# ESP32.net
KiCad netlist of a schematic drawn in Altium Designer
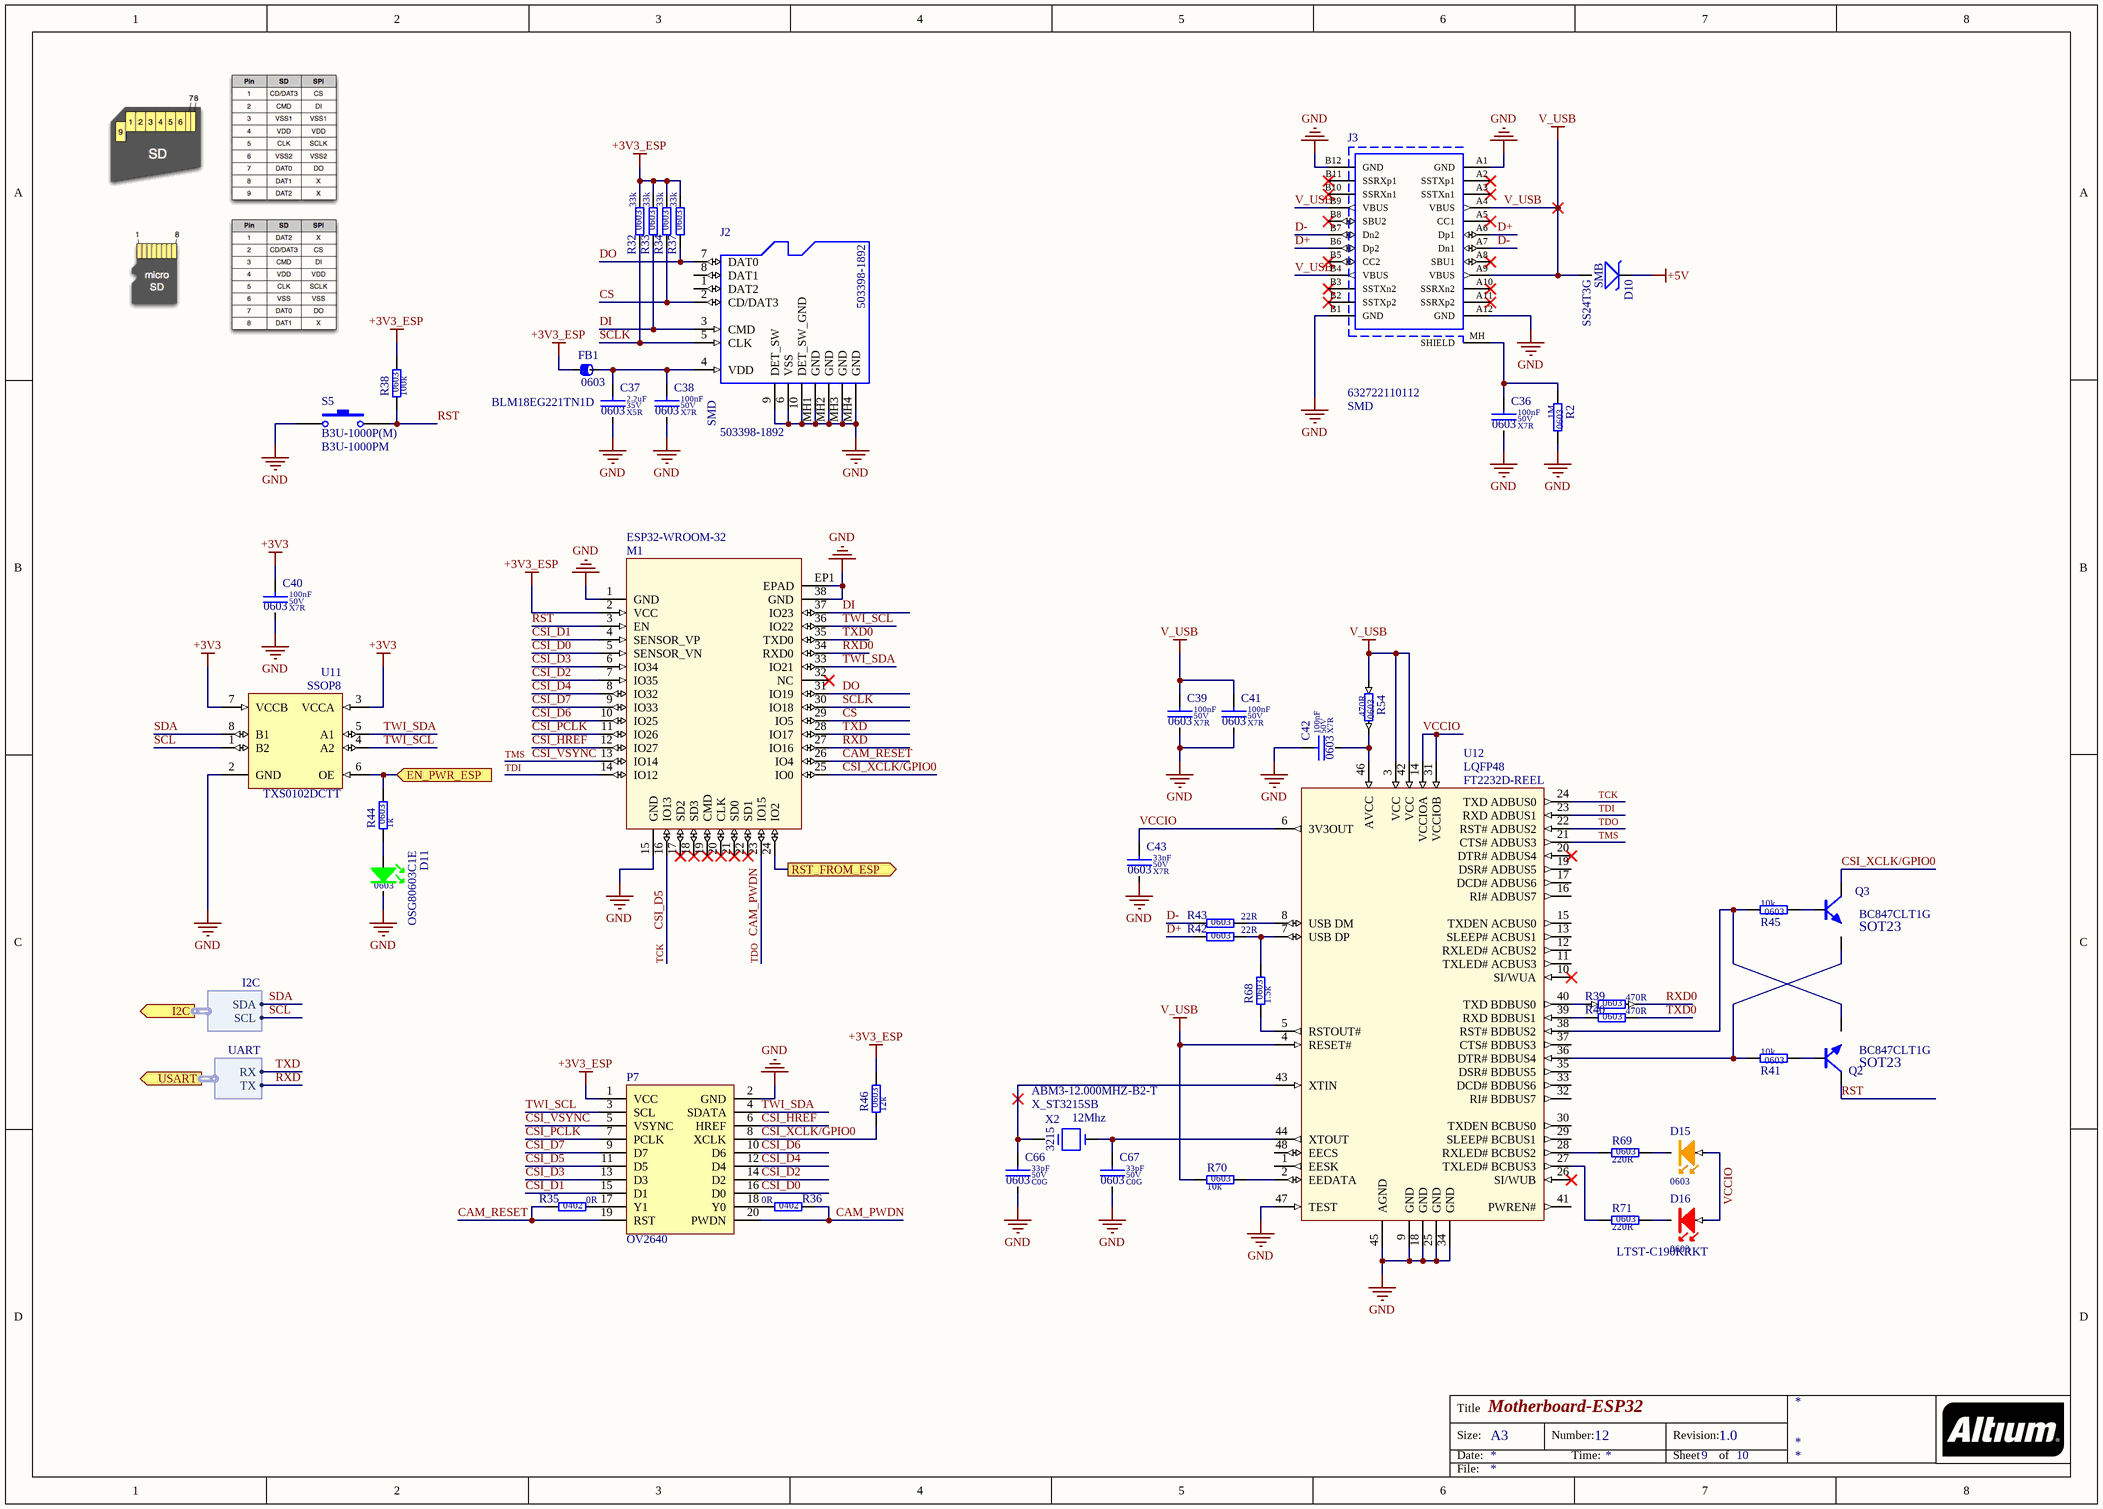
[diagram p0: ESP32.SchDoc]

(export (version "E")
  (design (tool "Eeschema 10.0.6"))
  (components
    (comp (ref "C36")
      (value "100nF")
      (footprint "C_0603_1608")
      (description "Capacitor")
      (fields
        (field (name "DIELECTRIC") "X7R")
        (field (name "VOLTAGE") "50V")
        (field (name "SCH_FOOTPRINT") "0603")
        (field (name "PART NUMBER") "C_100nF_50V_X7R_0603_5")
        (field (name "MANUFACTURER") "Samsung")
      )
      (libsource (lib "Library") (part "C"))
    )
    (comp (ref "C37")
      (value "2.2uF")
      (footprint "C_0603_1608")
      (description "Capacitor")
      (fields
        (field (name "DIELECTRIC") "X5R")
        (field (name "VOLTAGE") "35V")
        (field (name "SCH_FOOTPRINT") "0603")
        (field (name "PART NUMBER") "C_2.2uF_35V_X5R_0603_10")
        (field (name "MANUFACTURER") "Murata")
      )
      (libsource (lib "Library") (part "C"))
    )
    (comp (ref "C38")
      (value "100nF")
      (footprint "C_0603_1608")
      (description "Capacitor")
      (fields
        (field (name "DIELECTRIC") "X7R")
        (field (name "VOLTAGE") "50V")
        (field (name "SCH_FOOTPRINT") "0603")
        (field (name "PART NUMBER") "C_100nF_50V_X7R_0603_5")
        (field (name "MANUFACTURER") "Samsung")
      )
      (libsource (lib "Library") (part "C"))
    )
    (comp (ref "C39")
      (value "100nF")
      (footprint "C_0603_1608")
      (description "Capacitor")
      (fields
        (field (name "DIELECTRIC") "X7R")
        (field (name "VOLTAGE") "50V")
        (field (name "SCH_FOOTPRINT") "0603")
        (field (name "PART NUMBER") "C_100nF_50V_X7R_0603_5")
        (field (name "MANUFACTURER") "Samsung")
      )
      (libsource (lib "Library") (part "C"))
    )
    (comp (ref "C40")
      (value "100nF")
      (footprint "C_0603_1608")
      (description "Capacitor")
      (fields
        (field (name "DIELECTRIC") "X7R")
        (field (name "VOLTAGE") "50V")
        (field (name "SCH_FOOTPRINT") "0603")
        (field (name "PART NUMBER") "C_100nF_50V_X7R_0603_5")
        (field (name "MANUFACTURER") "Samsung")
      )
      (libsource (lib "Library") (part "C"))
    )
    (comp (ref "C41")
      (value "100nF")
      (footprint "C_0603_1608")
      (description "Capacitor")
      (fields
        (field (name "DIELECTRIC") "X7R")
        (field (name "VOLTAGE") "50V")
        (field (name "SCH_FOOTPRINT") "0603")
        (field (name "PART NUMBER") "C_100nF_50V_X7R_0603_5")
        (field (name "MANUFACTURER") "Samsung")
      )
      (libsource (lib "Library") (part "C"))
    )
    (comp (ref "C42")
      (value "100nF")
      (footprint "C_0603_1608")
      (description "Capacitor")
      (fields
        (field (name "DIELECTRIC") "X7R")
        (field (name "VOLTAGE") "50V")
        (field (name "SCH_FOOTPRINT") "0603")
        (field (name "PART NUMBER") "C_100nF_50V_X7R_0603_5")
        (field (name "MANUFACTURER") "Samsung")
      )
      (libsource (lib "Library") (part "C"))
    )
    (comp (ref "C43")
      (value "33nF")
      (footprint "C_0603_1608")
      (description "Capacitor")
      (fields
        (field (name "DIELECTRIC") "X7R")
        (field (name "VOLTAGE") "50V")
        (field (name "SCH_FOOTPRINT") "0603")
        (field (name "PART NUMBER") "C_33nF_50V_X7R_0603_10")
        (field (name "MANUFACTURER") "Yageo")
      )
      (libsource (lib "Library") (part "C"))
    )
    (comp (ref "C66")
      (value "33pF")
      (footprint "C_0603_1608")
      (description "Capacitor")
      (fields
        (field (name "DIELECTRIC") "C0G")
        (field (name "VOLTAGE") "50V")
        (field (name "SCH_FOOTPRINT") "0603")
        (field (name "PART NUMBER") "C_33pF_50V_C0G_0603_5")
        (field (name "MANUFACTURER") "AVX")
      )
      (libsource (lib "Library") (part "C"))
    )
    (comp (ref "C67")
      (value "33pF")
      (footprint "C_0603_1608")
      (description "Capacitor")
      (fields
        (field (name "DIELECTRIC") "C0G")
        (field (name "VOLTAGE") "50V")
        (field (name "SCH_FOOTPRINT") "0603")
        (field (name "PART NUMBER") "C_33pF_50V_C0G_0603_5")
        (field (name "MANUFACTURER") "AVX")
      )
      (libsource (lib "Library") (part "C"))
    )
    (comp (ref "D10")
      (value "SS24T3G")
      (footprint "SMB_DO-214AA")
      (fields
        (field (name "SCH_FOOTPRINT") "SMB")
        (field (name "PART NUMBER") "DS_SS24_2A_40V_SMB")
        (field (name "VOLTAGE") "40V")
        (field (name "MANUFACTURER") "ON Semiconductor")
      )
      (libsource (lib "Library") (part "DS"))
    )
    (comp (ref "D11")
      (value "OSG80603C1E")
      (footprint "OL_0603_1608")
      (description "LED GREEN")
      (fields
        (field (name "SCH_FOOTPRINT") "0603")
        (field (name "PART NUMBER") "OL_G_0603_OSG80603C1E")
        (field (name "MANUFACTURER") "Optosupply")
      )
      (libsource (lib "Library") (part "OL_G"))
    )
    (comp (ref "D15")
      (value "OL_O")
      (footprint "OL_0603_1608")
      (description "LED_RED")
      (fields (field (name "PART NUMBER") "OL_O_0603") (field (name "SCH_FOOTPRINT") "0603"))
      (libsource (lib "Library") (part "OL_O"))
    )
    (comp (ref "D16")
      (value "LTST-C190KRKT")
      (footprint "OL_0603_1608")
      (description "LED_RED")
      (fields
        (field (name "PART NUMBER") "OL_R_0603")
        (field (name "SCH_FOOTPRINT") "0603")
        (field (name "MANUFACTURER") "Lite-On")
      )
      (libsource (lib "Library") (part "OL_R"))
    )
    (comp (ref "FB1")
      (value "BLM18EG221TN1D")
      (footprint "FB_0603_1608")
      (description "Ferrite Bead")
      (fields
        (field (name "PART NUMBER") "FB_BLM18EG221TN1D")
        (field (name "SCH_FOOTPRINT") "0603")
        (field (name "MANUFACTURER") "Murata")
      )
      (libsource (lib "Library") (part "FB"))
    )
    (comp (ref "J2")
      (value "503398-1892")
      (footprint "503398-1892")
      (description "J_MICRO_SD")
      (fields
        (field (name "SCH_FOOTPRINT") "SMD")
        (field (name "MANUFACTURER PART NUMBER") "503398-1892")
        (field (name "PART NUMBER") "J_MICRO_SD_503398-1892")
        (field (name "MANUFACTURER") "Molex")
      )
      (libsource (lib "Library") (part "J_MICRO_SD_503398-1892"))
    )
    (comp (ref "J3")
      (value "632722110112")
      (footprint "J_USB_C_3.1_Vertical")
      (fields
        (field (name "PART NUMBER") "J_USB_C_3.1_Vertical")
        (field (name "SCH_FOOTPRINT") "SMD")
        (field (name "MANUFACTURER") "Wurth")
        (field (name "Comment") "USB C Connector")
      )
      (libsource (lib "Library") (part "J_USB_3.1_C"))
    )
    (comp (ref "M1")
      (value "ESP32-WROOM-32")
      (footprint "MOD_ESP_WROOM_32")
      (fields
        (field (name "PART NUMBER") "MOD_ESP32-WROOM-32")
        (field (name "MANUFACTURER") "ESPRESSIF")
        (field (name "Comment") "2.4 GHz Wi-Fi-and-Bluetooth combo chip")
      )
      (libsource (lib "Library") (part "MOD_ESP_WROOM_32"))
    )
    (comp (ref "P7")
      (value "OV2640")
      (footprint "H2X10_OV2640")
      (description "Header, 11-Pin, Dual row, Right Angle")
      (fields (field (name "PUBLISHER") "Altium Limited"))
      (libsource (lib "Patryk_ROZNE") (part "OV2640"))
    )
    (comp (ref "Q2")
      (value "BC847CLT1G")
      (footprint "SOT23_TO236_SC59")
      (fields
        (field (name "PART NUMBER") "QNP_BC847C_45V_0A1")
        (field (name "SCH_FOOTPRINT") "SOT23")
        (field (name "VOLTAGE") "45V")
        (field (name "MANUFACTURER") "ON Semiconductor")
      )
      (libsource (lib "Library") (part "QNP_BEC"))
    )
    (comp (ref "Q3")
      (value "BC847CLT1G")
      (footprint "SOT23_TO236_SC59")
      (fields
        (field (name "PART NUMBER") "QNP_BC847C_45V_0A1")
        (field (name "SCH_FOOTPRINT") "SOT23")
        (field (name "VOLTAGE") "45V")
        (field (name "MANUFACTURER") "ON Semiconductor")
      )
      (libsource (lib "Library") (part "QNP_BEC"))
    )
    (comp (ref "R2")
      (value "1M")
      (footprint "R_0603_1608")
      (fields
        (field (name "SCH_FOOTPRINT") "0603")
        (field (name "PART NUMBER") "R_1M_0603_1")
        (field (name "VOLTAGE") "50V")
        (field (name "POWER") "100mW")
      )
      (libsource (lib "Library") (part "R"))
    )
    (comp (ref "R32")
      (value "33k")
      (footprint "R_0603_1608")
      (fields
        (field (name "SCH_FOOTPRINT") "0603")
        (field (name "PART NUMBER") "R_33k_0603_1")
        (field (name "VOLTAGE") "75V")
        (field (name "POWER") "100mW")
      )
      (libsource (lib "Library") (part "R"))
    )
    (comp (ref "R33")
      (value "33k")
      (footprint "R_0603_1608")
      (fields
        (field (name "SCH_FOOTPRINT") "0603")
        (field (name "PART NUMBER") "R_33k_0603_1")
        (field (name "VOLTAGE") "75V")
        (field (name "POWER") "100mW")
      )
      (libsource (lib "Library") (part "R"))
    )
    (comp (ref "R34")
      (value "33k")
      (footprint "R_0603_1608")
      (fields
        (field (name "SCH_FOOTPRINT") "0603")
        (field (name "PART NUMBER") "R_33k_0603_1")
        (field (name "VOLTAGE") "75V")
        (field (name "POWER") "100mW")
      )
      (libsource (lib "Library") (part "R"))
    )
    (comp (ref "R35")
      (value "0R")
      (footprint "R_0402_1005")
      (fields
        (field (name "SCH_FOOTPRINT") "0402")
        (field (name "PART NUMBER") "R_0R_0402_5")
        (field (name "VOLTAGE") "50V")
        (field (name "POWER") "63mW")
      )
      (libsource (lib "Library") (part "R"))
    )
    (comp (ref "R36")
      (value "0R")
      (footprint "R_0402_1005")
      (fields
        (field (name "SCH_FOOTPRINT") "0402")
        (field (name "PART NUMBER") "R_0R_0402_5")
        (field (name "VOLTAGE") "50V")
        (field (name "POWER") "63mW")
      )
      (libsource (lib "Library") (part "R"))
    )
    (comp (ref "R37")
      (value "33k")
      (footprint "R_0603_1608")
      (fields
        (field (name "SCH_FOOTPRINT") "0603")
        (field (name "PART NUMBER") "R_33k_0603_1")
        (field (name "VOLTAGE") "75V")
        (field (name "POWER") "100mW")
      )
      (libsource (lib "Library") (part "R"))
    )
    (comp (ref "R38")
      (value "100k")
      (footprint "R_0603_1608")
      (fields
        (field (name "SCH_FOOTPRINT") "0603")
        (field (name "PART NUMBER") "R_100k_0603_1")
        (field (name "VOLTAGE") "50V")
        (field (name "POWER") "100mW")
      )
      (libsource (lib "Library") (part "R"))
    )
    (comp (ref "R39")
      (value "470R")
      (footprint "R_0603_1608")
      (fields
        (field (name "SCH_FOOTPRINT") "0603")
        (field (name "PART NUMBER") "R_470R_0603_1")
        (field (name "VOLTAGE") "50V")
        (field (name "POWER") "100mW")
      )
      (libsource (lib "") (part "R_2"))
    )
    (comp (ref "R40")
      (value "470R")
      (footprint "R_0603_1608")
      (fields
        (field (name "SCH_FOOTPRINT") "0603")
        (field (name "PART NUMBER") "R_470R_0603_1")
        (field (name "VOLTAGE") "50V")
        (field (name "POWER") "100mW")
      )
      (libsource (lib "") (part "R_1"))
    )
    (comp (ref "R41")
      (value "10k")
      (footprint "R_0603_1608")
      (fields
        (field (name "SCH_FOOTPRINT") "0603")
        (field (name "PART NUMBER") "R_10k_0603_1")
        (field (name "VOLTAGE") "75V")
        (field (name "POWER") "100mW")
      )
      (libsource (lib "Library") (part "R"))
    )
    (comp (ref "R42")
      (value "22R")
      (footprint "R_0603_1608")
      (fields
        (field (name "SCH_FOOTPRINT") "0603")
        (field (name "PART NUMBER") "R_22R_0603_5")
        (field (name "VOLTAGE") "50V")
        (field (name "POWER") "125mW")
      )
      (libsource (lib "Library") (part "R"))
    )
    (comp (ref "R43")
      (value "22R")
      (footprint "R_0603_1608")
      (fields
        (field (name "SCH_FOOTPRINT") "0603")
        (field (name "PART NUMBER") "R_22R_0603_5")
        (field (name "VOLTAGE") "50V")
        (field (name "POWER") "125mW")
      )
      (libsource (lib "Library") (part "R"))
    )
    (comp (ref "R44")
      (value "1k")
      (footprint "R_0603_1608")
      (fields
        (field (name "SCH_FOOTPRINT") "0603")
        (field (name "PART NUMBER") "R_1k_0603_1")
        (field (name "VOLTAGE") "75V")
        (field (name "POWER") "100mW")
      )
      (libsource (lib "Library") (part "R"))
    )
    (comp (ref "R45")
      (value "10k")
      (footprint "R_0603_1608")
      (fields
        (field (name "SCH_FOOTPRINT") "0603")
        (field (name "PART NUMBER") "R_10k_0603_1")
        (field (name "VOLTAGE") "75V")
        (field (name "POWER") "100mW")
      )
      (libsource (lib "Library") (part "R"))
    )
    (comp (ref "R46")
      (value "12k")
      (footprint "R_0603_1608")
      (fields
        (field (name "SCH_FOOTPRINT") "0603")
        (field (name "PART NUMBER") "R_12k_0603_1")
        (field (name "VOLTAGE") "50V")
        (field (name "POWER") "100mW")
      )
      (libsource (lib "Library") (part "R"))
    )
    (comp (ref "R54")
      (value "470R")
      (footprint "R_0603_1608")
      (fields
        (field (name "SCH_FOOTPRINT") "0603")
        (field (name "PART NUMBER") "R_470R_0603_1")
        (field (name "VOLTAGE") "50V")
        (field (name "POWER") "100mW")
      )
      (libsource (lib "") (part "R_2"))
    )
    (comp (ref "R68")
      (value "1.5k")
      (footprint "R_0603_1608")
      (fields
        (field (name "SCH_FOOTPRINT") "0603")
        (field (name "PART NUMBER") "R_1.5k_0603_1")
        (field (name "VOLTAGE") "50V")
        (field (name "POWER") "100mW")
      )
      (libsource (lib "Library") (part "R"))
    )
    (comp (ref "R69")
      (value "220R")
      (footprint "R_0603_1608")
      (fields
        (field (name "SCH_FOOTPRINT") "0603")
        (field (name "PART NUMBER") "R_220R_0603_1")
        (field (name "VOLTAGE") "50V")
        (field (name "POWER") "100mW")
      )
      (libsource (lib "Library") (part "R"))
    )
    (comp (ref "R70")
      (value "10k")
      (footprint "R_0603_1608")
      (fields
        (field (name "SCH_FOOTPRINT") "0603")
        (field (name "PART NUMBER") "R_10k_0603_1")
        (field (name "VOLTAGE") "75V")
        (field (name "POWER") "100mW")
      )
      (libsource (lib "Library") (part "R"))
    )
    (comp (ref "R71")
      (value "220R")
      (footprint "R_0603_1608")
      (fields
        (field (name "SCH_FOOTPRINT") "0603")
        (field (name "PART NUMBER") "R_220R_0603_1")
        (field (name "VOLTAGE") "50V")
        (field (name "POWER") "100mW")
      )
      (libsource (lib "Library") (part "R"))
    )
    (comp (ref "S5")
      (value "B3U-1000PM")
      (footprint "B3U-1000P")
      (description "Tact Switch")
      (fields
        (field (name "PART NUMBER") "S_B3U-1000PM")
        (field (name "SCH_FOOTPRINT") "B3U-1000P(M)")
        (field (name "MANUFACTURER") "OMRON")
      )
      (libsource (lib "Library") (part "S_TACTSWITCH"))
    )
    (comp (ref "U11")
      (value "TXS0102DCTT")
      (footprint "SSOP8_3x3")
      (fields
        (field (name "SCH_FOOTPRINT") "SSOP8")
        (field (name "PART NUMBER") "U_TXS0102DCTT")
        (field (name "MANUFACTURER") "Texas Instruments")
      )
      (libsource (lib "Library") (part "U_TXS0102_DCT_DCU"))
    )
    (comp (ref "U12")
      (value "FT2232D-REEL")
      (footprint "LQFP48_7x7")
      (description "FTDI")
      (fields
        (field (name "SCH_FOOTPRINT") "LQFP48")
        (field (name "PART NUMBER") "U_FT2232D")
        (field (name "Comment") "FT2232D")
      )
      (libsource (lib "Library") (part "U_FT2232D"))
    )
    (comp (ref "X2")
      (value "12Mhz")
      (footprint "X_ABM3-12.000MHZ-B2-T")
      (fields
        (field (name "PART NUMBER") "X_ABM3-12.000MHZ-B2-T")
        (field (name "MANUFACTURER PART NUMBER") "ABM3-12.000MHZ-B2-T")
        (field (name "SCH_FOOTPRINT") "X_ST3215SB")
        (field (name "MANUFACTURER") "ABM3")
        (field (name "Comment") "X_ST3215SB")
      )
      (libsource (lib "Library") (part "X_ST3215SB"))
    )
  )
  (nets
    (net (code "3") (name "+3V3") (class "Default")
      (node (ref "C40") (pin "1") (pinfunction "1_1") (pintype "passive"))
      (node (ref "U11") (pin "3") (pinfunction "VCCA_3") (pintype "input"))
      (node (ref "U11") (pin "7") (pinfunction "VCCB_7") (pintype "input"))
    )
    (net (code "4") (name "+3V3_ESP") (class "Default")
      (node (ref "FB1") (pin "1") (pintype "passive"))
      (node (ref "M1") (pin "2") (pinfunction "VCC_2") (pintype "input"))
      (node (ref "P7") (pin "1") (pinfunction "VCC_1") (pintype "passive"))
      (node (ref "R32") (pin "2") (pinfunction "2_2") (pintype "passive"))
      (node (ref "R33") (pin "2") (pinfunction "2_2") (pintype "passive"))
      (node (ref "R34") (pin "2") (pinfunction "2_2") (pintype "passive"))
      (node (ref "R37") (pin "2") (pinfunction "2_2") (pintype "passive"))
      (node (ref "R38") (pin "2") (pinfunction "2_2") (pintype "passive"))
      (node (ref "R46") (pin "2") (pinfunction "2_2") (pintype "passive"))
    )
    (net (code "5") (name "+5V") (class "Default") (node (ref "D10") (pin "1") (pintype "passive")))
    (net (code "6") (name "/CAM_PWDN") (class "Default")
      (node (ref "M1") (pin "23") (pinfunction "IO15_23") (pintype "bidirectional"))
      (node (ref "P7") (pin "20") (pinfunction "PWDN_20") (pintype "passive"))
      (node (ref "R36") (pin "2") (pinfunction "2_2") (pintype "passive"))
      (node (ref "U12") (pin "22") (pinfunction "RST#_ADBUS2_22") (pintype "input"))
    )
    (net (code "7") (name "/CAM_RESET") (class "Default")
      (node (ref "M1") (pin "26") (pinfunction "IO4_26") (pintype "bidirectional"))
      (node (ref "P7") (pin "19") (pinfunction "RST_19") (pintype "passive"))
      (node (ref "R35") (pin "1") (pinfunction "1_1") (pintype "passive"))
    )
    (net (code "8") (name "/CS") (class "Default")
      (node (ref "J2") (pin "2") (pinfunction "CD/DAT3_2") (pintype "bidirectional"))
      (node (ref "M1") (pin "29") (pinfunction "IO5_29") (pintype "bidirectional"))
      (node (ref "R34") (pin "1") (pinfunction "1_1") (pintype "passive"))
    )
    (net (code "9") (name "/CSI_D0") (class "Default")
      (node (ref "M1") (pin "5") (pinfunction "SENSOR_VN_5") (pintype "input"))
      (node (ref "P7") (pin "16") (pinfunction "D0_16") (pintype "passive"))
    )
    (net (code "10") (name "/CSI_D1") (class "Default")
      (node (ref "M1") (pin "4") (pinfunction "SENSOR_VP_4") (pintype "input"))
      (node (ref "P7") (pin "15") (pinfunction "D1_15") (pintype "passive"))
    )
    (net (code "11") (name "/CSI_D2") (class "Default")
      (node (ref "M1") (pin "7") (pinfunction "IO35_7") (pintype "input"))
      (node (ref "P7") (pin "14") (pinfunction "D2_14") (pintype "passive"))
    )
    (net (code "12") (name "/CSI_D3") (class "Default")
      (node (ref "M1") (pin "6") (pinfunction "IO34_6") (pintype "input"))
      (node (ref "P7") (pin "13") (pinfunction "D3_13") (pintype "passive"))
    )
    (net (code "13") (name "/CSI_D4") (class "Default")
      (node (ref "M1") (pin "8") (pinfunction "IO32_8") (pintype "bidirectional"))
      (node (ref "P7") (pin "12") (pinfunction "D4_12") (pintype "passive"))
    )
    (net (code "14") (name "/CSI_D5") (class "Default")
      (node (ref "M1") (pin "16") (pinfunction "IO13_16") (pintype "bidirectional"))
      (node (ref "P7") (pin "11") (pinfunction "D5_11") (pintype "passive"))
      (node (ref "U12") (pin "24") (pinfunction "TXD_ADBUS0_24") (pintype "output"))
    )
    (net (code "15") (name "/CSI_D6") (class "Default")
      (node (ref "M1") (pin "10") (pinfunction "IO25_10") (pintype "bidirectional"))
      (node (ref "P7") (pin "10") (pinfunction "D6_10") (pintype "passive"))
    )
    (net (code "16") (name "/CSI_D7") (class "Default")
      (node (ref "M1") (pin "9") (pinfunction "IO33_9") (pintype "bidirectional"))
      (node (ref "P7") (pin "9") (pinfunction "D7_9") (pintype "passive"))
    )
    (net (code "17") (name "/CSI_HREF") (class "Default")
      (node (ref "M1") (pin "12") (pinfunction "IO27_12") (pintype "bidirectional"))
      (node (ref "P7") (pin "6") (pinfunction "HREF_6") (pintype "passive"))
    )
    (net (code "18") (name "/CSI_PCLK") (class "Default")
      (node (ref "M1") (pin "11") (pinfunction "IO26_11") (pintype "bidirectional"))
      (node (ref "P7") (pin "7") (pinfunction "PCLK_7") (pintype "passive"))
    )
    (net (code "19") (name "/CSI_VSYNC") (class "Default")
      (node (ref "M1") (pin "13") (pinfunction "IO14_13") (pintype "bidirectional"))
      (node (ref "P7") (pin "5") (pinfunction "VSYNC_5") (pintype "passive"))
      (node (ref "U12") (pin "21") (pinfunction "CTS#_ADBUS3_21") (pintype "output"))
    )
    (net (code "20") (name "/CSI_XCLK{slash}GPIO0") (class "Default")
      (node (ref "M1") (pin "25") (pinfunction "IO0_25") (pintype "bidirectional"))
      (node (ref "P7") (pin "8") (pinfunction "XCLK_8") (pintype "passive"))
      (node (ref "Q3") (pin "3") (pinfunction "C_3") (pintype "passive"))
      (node (ref "R46") (pin "1") (pinfunction "1_1") (pintype "passive"))
    )
    (net (code "21") (name "/D+") (class "Default")
      (node (ref "J3") (pin "A6") (pinfunction "Dp1_A6") (pintype "bidirectional"))
      (node (ref "J3") (pin "B6") (pinfunction "Dp2_B6") (pintype "bidirectional"))
      (node (ref "R42") (pin "1") (pinfunction "1_1") (pintype "passive"))
    )
    (net (code "22") (name "/D-") (class "Default")
      (node (ref "J3") (pin "A7") (pinfunction "Dn1_A7") (pintype "bidirectional"))
      (node (ref "J3") (pin "B7") (pinfunction "Dn2_B7") (pintype "bidirectional"))
      (node (ref "R43") (pin "1") (pinfunction "1_1") (pintype "passive"))
    )
    (net (code "23") (name "/DI") (class "Default")
      (node (ref "J2") (pin "3") (pinfunction "CMD_3") (pintype "input"))
      (node (ref "M1") (pin "37") (pinfunction "IO23_37") (pintype "bidirectional"))
      (node (ref "R33") (pin "1") (pinfunction "1_1") (pintype "passive"))
    )
    (net (code "24") (name "/DO") (class "Default")
      (node (ref "J2") (pin "7") (pinfunction "DAT0_7") (pintype "bidirectional"))
      (node (ref "M1") (pin "31") (pinfunction "IO19_31") (pintype "bidirectional"))
      (node (ref "R37") (pin "1") (pinfunction "1_1") (pintype "passive"))
    )
    (net (code "25") (name "/EN_PWR_ESP") (class "Default")
      (node (ref "R44") (pin "2") (pinfunction "2_2") (pintype "passive"))
      (node (ref "U11") (pin "6") (pinfunction "OE_6") (pintype "input"))
    )
    (net (code "26") (name "/RST") (class "Default")
      (node (ref "M1") (pin "3") (pinfunction "EN_3") (pintype "input"))
      (node (ref "Q2") (pin "3") (pinfunction "C_3") (pintype "passive"))
      (node (ref "R38") (pin "1") (pinfunction "1_1") (pintype "passive"))
      (node (ref "S5") (pin "2") (pinfunction "2_2") (pintype "passive"))
    )
    (net (code "27") (name "/RST_FROM_ESP") (class "Default")
      (node (ref "M1") (pin "24") (pinfunction "IO2_24") (pintype "bidirectional"))
    )
    (net (code "28") (name "/RXD") (class "Default")
      (node (ref "M1") (pin "27") (pinfunction "IO16_27") (pintype "bidirectional"))
    )
    (net (code "29") (name "/RXD0") (class "Default")
      (node (ref "M1") (pin "34") (pinfunction "RXD0_34") (pintype "bidirectional"))
      (node (ref "R39") (pin "2") (pinfunction "2_2") (pintype "output"))
    )
    (net (code "30") (name "/SCL") (class "Default")
      (node (ref "U11") (pin "1") (pinfunction "B2_1") (pintype "bidirectional"))
    )
    (net (code "31") (name "/SCLK") (class "Default")
      (node (ref "J2") (pin "5") (pinfunction "CLK_5") (pintype "input"))
      (node (ref "M1") (pin "30") (pinfunction "IO18_30") (pintype "bidirectional"))
      (node (ref "R32") (pin "1") (pinfunction "1_1") (pintype "passive"))
    )
    (net (code "32") (name "/SDA") (class "Default")
      (node (ref "U11") (pin "8") (pinfunction "B1_8") (pintype "bidirectional"))
    )
    (net (code "33") (name "/TDI") (class "Default")
      (node (ref "M1") (pin "14") (pinfunction "IO12_14") (pintype "bidirectional"))
      (node (ref "U12") (pin "23") (pinfunction "RXD_ADBUS1_23") (pintype "input"))
    )
    (net (code "34") (name "/TWI_SCL") (class "Default")
      (node (ref "M1") (pin "36") (pinfunction "IO22_36") (pintype "bidirectional"))
      (node (ref "P7") (pin "3") (pinfunction "SCL_3") (pintype "passive"))
      (node (ref "U11") (pin "4") (pinfunction "A2_4") (pintype "bidirectional"))
    )
    (net (code "35") (name "/TWI_SDA") (class "Default")
      (node (ref "M1") (pin "33") (pinfunction "IO21_33") (pintype "bidirectional"))
      (node (ref "P7") (pin "4") (pinfunction "SDATA_4") (pintype "passive"))
      (node (ref "U11") (pin "5") (pinfunction "A1_5") (pintype "bidirectional"))
    )
    (net (code "36") (name "/TXD") (class "Default")
      (node (ref "M1") (pin "28") (pinfunction "IO17_28") (pintype "bidirectional"))
    )
    (net (code "37") (name "/TXD0") (class "Default")
      (node (ref "M1") (pin "35") (pinfunction "TXD0_35") (pintype "bidirectional"))
      (node (ref "R40") (pin "2") (pinfunction "2_2") (pintype "bidirectional"))
    )
    (net (code "38") (name "/VCCIO") (class "Default")
      (node (ref "C43") (pin "1") (pinfunction "1_1") (pintype "passive"))
      (node (ref "D15") (pin "2") (pinfunction "A_2") (pintype "input"))
      (node (ref "D16") (pin "2") (pinfunction "A_2") (pintype "input"))
      (node (ref "U12") (pin "14") (pinfunction "VCCIOA_14") (pintype "input"))
      (node (ref "U12") (pin "31") (pinfunction "VCCIOB_31") (pintype "input"))
      (node (ref "U12") (pin "6") (pinfunction "3V3OUT_6") (pintype "output"))
    )
    (net (code "41") (name "GND") (class "Default")
      (node (ref "C36") (pin "2") (pinfunction "2_2") (pintype "passive"))
      (node (ref "C37") (pin "2") (pinfunction "2_2") (pintype "passive"))
      (node (ref "C38") (pin "2") (pinfunction "2_2") (pintype "passive"))
      (node (ref "C39") (pin "2") (pinfunction "2_2") (pintype "passive"))
      (node (ref "C40") (pin "2") (pinfunction "2_2") (pintype "passive"))
      (node (ref "C41") (pin "2") (pinfunction "2_2") (pintype "passive"))
      (node (ref "C42") (pin "1") (pinfunction "1_1") (pintype "passive"))
      (node (ref "C43") (pin "2") (pinfunction "2_2") (pintype "passive"))
      (node (ref "C66") (pin "2") (pinfunction "2_2") (pintype "passive"))
      (node (ref "C67") (pin "2") (pinfunction "2_2") (pintype "passive"))
      (node (ref "D11") (pin "1") (pinfunction "K_1") (pintype "passive"))
      (node (ref "J2") (pin "10") (pinfunction "DET_SW_GND_10") (pintype "power_in"))
      (node (ref "J2") (pin "6") (pinfunction "VSS_6") (pintype "power_in"))
      (node (ref "J2") (pin "9") (pinfunction "DET_SW_9") (pintype "passive"))
      (node (ref "J2") (pin "MH1") (pinfunction "GND_MH1") (pintype "power_in"))
      (node (ref "J2") (pin "MH2") (pinfunction "GND_MH2") (pintype "power_in"))
      (node (ref "J2") (pin "MH3") (pinfunction "GND_MH3") (pintype "power_in"))
      (node (ref "J2") (pin "MH4") (pinfunction "GND_MH4") (pintype "power_in"))
      (node (ref "J3") (pin "A1") (pinfunction "GND_A1") (pintype "power_in"))
      (node (ref "J3") (pin "A12") (pinfunction "GND_A12") (pintype "power_in"))
      (node (ref "J3") (pin "B1") (pinfunction "GND_B1") (pintype "power_in"))
      (node (ref "J3") (pin "B12") (pinfunction "GND_B12") (pintype "power_in"))
      (node (ref "M1") (pin "1") (pinfunction "GND_1") (pintype "power_in"))
      (node (ref "M1") (pin "15") (pinfunction "GND_15") (pintype "power_in"))
      (node (ref "M1") (pin "38") (pinfunction "GND_38") (pintype "power_in"))
      (node (ref "M1") (pin "EP1") (pinfunction "EPAD_EP1") (pintype "power_in"))
      (node (ref "P7") (pin "2") (pinfunction "GND_2") (pintype "passive"))
      (node (ref "R2") (pin "2") (pinfunction "2_2") (pintype "passive"))
      (node (ref "S5") (pin "1") (pinfunction "1_1") (pintype "passive"))
      (node (ref "U11") (pin "2") (pinfunction "GND_2") (pintype "power_in"))
      (node (ref "U12") (pin "18") (pinfunction "GND_18") (pintype "power_in"))
      (node (ref "U12") (pin "25") (pinfunction "GND_25") (pintype "power_in"))
      (node (ref "U12") (pin "34") (pinfunction "GND_34") (pintype "power_in"))
      (node (ref "U12") (pin "45") (pinfunction "AGND_45") (pintype "power_in"))
      (node (ref "U12") (pin "47") (pinfunction "TEST_47") (pintype "input"))
      (node (ref "U12") (pin "9") (pinfunction "GND_9") (pintype "power_in"))
    )
    (net (code "42") (name "Net-(D11-A)") (class "Default")
      (node (ref "D11") (pin "2") (pinfunction "A_2") (pintype "passive"))
      (node (ref "R44") (pin "1") (pinfunction "1_1") (pintype "passive"))
    )
    (net (code "43") (name "Net-(D15-K)") (class "Default")
      (node (ref "D15") (pin "1") (pinfunction "K_1") (pintype "output"))
      (node (ref "R69") (pin "2") (pinfunction "2_2") (pintype "passive"))
    )
    (net (code "44") (name "Net-(D16-K)") (class "Default")
      (node (ref "D16") (pin "1") (pinfunction "K_1") (pintype "output"))
      (node (ref "R71") (pin "2") (pinfunction "2_2") (pintype "passive"))
    )
    (net (code "45") (name "Net-(J2-VDD)") (class "Default")
      (node (ref "C37") (pin "1") (pinfunction "1_1") (pintype "passive"))
      (node (ref "C38") (pin "1") (pinfunction "1_1") (pintype "passive"))
      (node (ref "FB1") (pin "2") (pintype "passive"))
      (node (ref "J2") (pin "4") (pinfunction "VDD_4") (pintype "input"))
    )
    (net (code "46") (name "Net-(J3-SHIELD)") (class "Default")
      (node (ref "C36") (pin "1") (pinfunction "1_1") (pintype "passive"))
      (node (ref "J3") (pin "MH") (pinfunction "SHIELD_MH") (pintype "passive"))
      (node (ref "R2") (pin "1") (pinfunction "1_1") (pintype "passive"))
    )
    (net (code "47") (name "Net-(P7-Y0)") (class "Default")
      (node (ref "P7") (pin "18") (pinfunction "Y0_18") (pintype "passive"))
      (node (ref "R36") (pin "1") (pinfunction "1_1") (pintype "passive"))
    )
    (net (code "48") (name "Net-(P7-Y1)") (class "Default")
      (node (ref "P7") (pin "17") (pinfunction "Y1_17") (pintype "passive"))
      (node (ref "R35") (pin "2") (pinfunction "2_2") (pintype "passive"))
    )
    (net (code "49") (name "Net-(Q2-B)") (class "Default")
      (node (ref "Q2") (pin "1") (pinfunction "B_1") (pintype "passive"))
      (node (ref "R41") (pin "2") (pinfunction "2_2") (pintype "passive"))
    )
    (net (code "50") (name "Net-(Q2-E)") (class "Default")
      (node (ref "Q2") (pin "2") (pinfunction "E_2") (pintype "passive"))
      (node (ref "R45") (pin "1") (pinfunction "1_1") (pintype "passive"))
      (node (ref "U12") (pin "38") (pinfunction "RST#_BDBUS2_38") (pintype "input"))
    )
    (net (code "51") (name "Net-(Q3-B)") (class "Default")
      (node (ref "Q3") (pin "1") (pinfunction "B_1") (pintype "passive"))
      (node (ref "R45") (pin "2") (pinfunction "2_2") (pintype "passive"))
    )
    (net (code "52") (name "Net-(Q3-E)") (class "Default")
      (node (ref "Q3") (pin "2") (pinfunction "E_2") (pintype "passive"))
      (node (ref "R41") (pin "1") (pinfunction "1_1") (pintype "passive"))
      (node (ref "U12") (pin "36") (pinfunction "DTR#_BDBUS4_36") (pintype "input"))
    )
    (net (code "53") (name "Net-(U12-AVCC)") (class "Default")
      (node (ref "C42") (pin "2") (pinfunction "2_2") (pintype "passive"))
      (node (ref "R54") (pin "2") (pinfunction "2_2") (pintype "output"))
      (node (ref "U12") (pin "46") (pinfunction "AVCC_46") (pintype "input"))
    )
    (net (code "54") (name "Net-(U12-EEDATA)") (class "Default")
      (node (ref "R70") (pin "2") (pinfunction "2_2") (pintype "passive"))
      (node (ref "U12") (pin "2") (pinfunction "EEDATA_2") (pintype "bidirectional"))
    )
    (net (code "55") (name "Net-(U12-RSTOUT#)") (class "Default")
      (node (ref "R68") (pin "1") (pinfunction "1_1") (pintype "passive"))
      (node (ref "U12") (pin "5") (pinfunction "RSTOUT#_5") (pintype "output"))
    )
    (net (code "56") (name "Net-(U12-RXD_BDBUS1)") (class "Default")
      (node (ref "R40") (pin "1") (pinfunction "1_1") (pintype "bidirectional"))
      (node (ref "U12") (pin "39") (pinfunction "RXD_BDBUS1_39") (pintype "input"))
    )
    (net (code "57") (name "Net-(U12-RXLED#_BCBUS2)") (class "Default")
      (node (ref "R69") (pin "1") (pinfunction "1_1") (pintype "passive"))
      (node (ref "U12") (pin "28") (pinfunction "RXLED#_BCBUS2_28") (pintype "output"))
    )
    (net (code "58") (name "Net-(U12-TXD_BDBUS0)") (class "Default")
      (node (ref "R39") (pin "1") (pinfunction "1_1") (pintype "input"))
      (node (ref "U12") (pin "40") (pinfunction "TXD_BDBUS0_40") (pintype "output"))
    )
    (net (code "59") (name "Net-(U12-TXLED#_BCBUS3)") (class "Default")
      (node (ref "R71") (pin "1") (pinfunction "1_1") (pintype "passive"))
      (node (ref "U12") (pin "27") (pinfunction "TXLED#_BCBUS3_27") (pintype "output"))
    )
    (net (code "60") (name "Net-(U12-USB_DM)") (class "Default")
      (node (ref "R43") (pin "2") (pinfunction "2_2") (pintype "passive"))
      (node (ref "U12") (pin "8") (pinfunction "USB_DM_8") (pintype "bidirectional"))
    )
    (net (code "61") (name "Net-(U12-USB_DP)") (class "Default")
      (node (ref "R42") (pin "2") (pinfunction "2_2") (pintype "passive"))
      (node (ref "R68") (pin "2") (pinfunction "2_2") (pintype "passive"))
      (node (ref "U12") (pin "7") (pinfunction "USB_DP_7") (pintype "bidirectional"))
    )
    (net (code "62") (name "Net-(U12-XTIN)") (class "Default")
      (node (ref "C66") (pin "1") (pinfunction "1_1") (pintype "passive"))
      (node (ref "U12") (pin "43") (pinfunction "XTIN_43") (pintype "input"))
      (node (ref "X2") (pin "1") (pinfunction "1_1") (pintype "passive"))
    )
    (net (code "63") (name "Net-(U12-XTOUT)") (class "Default")
      (node (ref "C67") (pin "1") (pinfunction "1_1") (pintype "passive"))
      (node (ref "U12") (pin "44") (pinfunction "XTOUT_44") (pintype "output"))
      (node (ref "X2") (pin "2") (pinfunction "2_2") (pintype "passive"))
    )
    (net (code "64") (name "V_USB") (class "Default")
      (node (ref "C39") (pin "1") (pinfunction "1_1") (pintype "passive"))
      (node (ref "C41") (pin "1") (pinfunction "1_1") (pintype "passive"))
      (node (ref "D10") (pin "2") (pintype "passive"))
      (node (ref "J3") (pin "A4") (pinfunction "VBUS_A4") (pintype "output"))
      (node (ref "J3") (pin "A9") (pinfunction "VBUS_A9") (pintype "output"))
      (node (ref "J3") (pin "B4") (pinfunction "VBUS_B4") (pintype "output"))
      (node (ref "J3") (pin "B9") (pinfunction "VBUS_B9") (pintype "output"))
      (node (ref "R54") (pin "1") (pinfunction "1_1") (pintype "input"))
      (node (ref "R70") (pin "1") (pinfunction "1_1") (pintype "passive"))
      (node (ref "U12") (pin "3") (pinfunction "VCC_3") (pintype "input"))
      (node (ref "U12") (pin "4") (pinfunction "RESET#_4") (pintype "input"))
      (node (ref "U12") (pin "42") (pinfunction "VCC_42") (pintype "input"))
    )
    (net (code "65") (name "unconnected-(J2-DAT1-Pad8)") (class "Default")
      (node (ref "J2") (pin "8") (pinfunction "DAT1_8") (pintype "bidirectional"))
    )
    (net (code "66") (name "unconnected-(J2-DAT2-Pad1)") (class "Default")
      (node (ref "J2") (pin "1") (pinfunction "DAT2_1") (pintype "bidirectional"))
    )
    (net (code "67") (name "unconnected-(J3-CC1-PadA5)") (class "Default")
      (node (ref "J3") (pin "A5") (pinfunction "CC1_A5") (pintype "passive+no_connect"))
    )
    (net (code "68") (name "unconnected-(J3-CC2-PadB5)") (class "Default")
      (node (ref "J3") (pin "B5") (pinfunction "CC2_B5") (pintype "bidirectional+no_connect"))
    )
    (net (code "69") (name "unconnected-(J3-SBU1-PadA8)") (class "Default")
      (node (ref "J3") (pin "A8") (pinfunction "SBU1_A8") (pintype "bidirectional+no_connect"))
    )
    (net (code "70") (name "unconnected-(J3-SBU2-PadB8)") (class "Default")
      (node (ref "J3") (pin "B8") (pinfunction "SBU2_B8") (pintype "bidirectional+no_connect"))
    )
    (net (code "71") (name "unconnected-(J3-SSRXn1-PadB10)") (class "Default")
      (node (ref "J3") (pin "B10") (pinfunction "SSRXn1_B10") (pintype "passive+no_connect"))
    )
    (net (code "72") (name "unconnected-(J3-SSRXn2-PadA10)") (class "Default")
      (node (ref "J3") (pin "A10") (pinfunction "SSRXn2_A10") (pintype "passive+no_connect"))
    )
    (net (code "73") (name "unconnected-(J3-SSRXp1-PadB11)") (class "Default")
      (node (ref "J3") (pin "B11") (pinfunction "SSRXp1_B11") (pintype "passive+no_connect"))
    )
    (net (code "74") (name "unconnected-(J3-SSRXp2-PadA11)") (class "Default")
      (node (ref "J3") (pin "A11") (pinfunction "SSRXp2_A11") (pintype "passive+no_connect"))
    )
    (net (code "75") (name "unconnected-(J3-SSTXn1-PadA3)") (class "Default")
      (node (ref "J3") (pin "A3") (pinfunction "SSTXn1_A3") (pintype "passive+no_connect"))
    )
    (net (code "76") (name "unconnected-(J3-SSTXn2-PadB3)") (class "Default")
      (node (ref "J3") (pin "B3") (pinfunction "SSTXn2_B3") (pintype "passive+no_connect"))
    )
    (net (code "77") (name "unconnected-(J3-SSTXp1-PadA2)") (class "Default")
      (node (ref "J3") (pin "A2") (pinfunction "SSTXp1_A2") (pintype "passive+no_connect"))
    )
    (net (code "78") (name "unconnected-(J3-SSTXp2-PadB2)") (class "Default")
      (node (ref "J3") (pin "B2") (pinfunction "SSTXp2_B2") (pintype "passive+no_connect"))
    )
    (net (code "79") (name "unconnected-(M1-CLK-Pad20)") (class "Default")
      (node (ref "M1") (pin "20") (pinfunction "CLK_20") (pintype "bidirectional+no_connect"))
    )
    (net (code "80") (name "unconnected-(M1-CMD-Pad19)") (class "Default")
      (node (ref "M1") (pin "19") (pinfunction "CMD_19") (pintype "bidirectional+no_connect"))
    )
    (net (code "81") (name "unconnected-(M1-NC-Pad32)") (class "Default")
      (node (ref "M1") (pin "32") (pinfunction "NC_32") (pintype "passive+no_connect"))
    )
    (net (code "82") (name "unconnected-(M1-SD0-Pad21)") (class "Default")
      (node (ref "M1") (pin "21") (pinfunction "SD0_21") (pintype "bidirectional+no_connect"))
    )
    (net (code "83") (name "unconnected-(M1-SD1-Pad22)") (class "Default")
      (node (ref "M1") (pin "22") (pinfunction "SD1_22") (pintype "bidirectional+no_connect"))
    )
    (net (code "84") (name "unconnected-(M1-SD2-Pad17)") (class "Default")
      (node (ref "M1") (pin "17") (pinfunction "SD2_17") (pintype "bidirectional+no_connect"))
    )
    (net (code "85") (name "unconnected-(M1-SD3-Pad18)") (class "Default")
      (node (ref "M1") (pin "18") (pinfunction "SD3_18") (pintype "bidirectional+no_connect"))
    )
    (net (code "86") (name "unconnected-(U12-CTS#_BDBUS3-Pad37)") (class "Default")
      (node (ref "U12") (pin "37") (pinfunction "CTS#_BDBUS3_37") (pintype "output"))
    )
    (net (code "87") (name "unconnected-(U12-DCD#_ADBUS6-Pad17)") (class "Default")
      (node (ref "U12") (pin "17") (pinfunction "DCD#_ADBUS6_17") (pintype "output"))
    )
    (net (code "88") (name "unconnected-(U12-DCD#_BDBUS6-Pad33)") (class "Default")
      (node (ref "U12") (pin "33") (pinfunction "DCD#_BDBUS6_33") (pintype "output"))
    )
    (net (code "89") (name "unconnected-(U12-DSR#_ADBUS5-Pad19)") (class "Default")
      (node (ref "U12") (pin "19") (pinfunction "DSR#_ADBUS5_19") (pintype "output"))
    )
    (net (code "90") (name "unconnected-(U12-DSR#_BDBUS5-Pad35)") (class "Default")
      (node (ref "U12") (pin "35") (pinfunction "DSR#_BDBUS5_35") (pintype "output"))
    )
    (net (code "91") (name "unconnected-(U12-DTR#_ADBUS4-Pad20)") (class "Default")
      (node (ref "U12") (pin "20") (pinfunction "DTR#_ADBUS4_20") (pintype "input+no_connect"))
    )
    (net (code "92") (name "unconnected-(U12-EECS-Pad48)") (class "Default")
      (node (ref "U12") (pin "48") (pinfunction "EECS_48") (pintype "bidirectional"))
    )
    (net (code "93") (name "unconnected-(U12-EESK-Pad1)") (class "Default")
      (node (ref "U12") (pin "1") (pinfunction "EESK_1") (pintype "output"))
    )
    (net (code "94") (name "unconnected-(U12-PWREN#-Pad41)") (class "Default")
      (node (ref "U12") (pin "41") (pinfunction "PWREN#_41") (pintype "output"))
    )
    (net (code "95") (name "unconnected-(U12-RI#_ADBUS7-Pad16)") (class "Default")
      (node (ref "U12") (pin "16") (pinfunction "RI#_ADBUS7_16") (pintype "output"))
    )
    (net (code "96") (name "unconnected-(U12-RI#_BDBUS7-Pad32)") (class "Default")
      (node (ref "U12") (pin "32") (pinfunction "RI#_BDBUS7_32") (pintype "output"))
    )
    (net (code "97") (name "unconnected-(U12-RXLED#_ACBUS2-Pad12)") (class "Default")
      (node (ref "U12") (pin "12") (pinfunction "RXLED#_ACBUS2_12") (pintype "output"))
    )
    (net (code "98") (name "unconnected-(U12-SI{slash}WUA-Pad10)") (class "Default")
      (node (ref "U12") (pin "10") (pinfunction "SI/WUA_10") (pintype "input+no_connect"))
    )
    (net (code "99") (name "unconnected-(U12-SI{slash}WUB-Pad26)") (class "Default")
      (node (ref "U12") (pin "26") (pinfunction "SI/WUB_26") (pintype "input+no_connect"))
    )
    (net (code "100") (name "unconnected-(U12-SLEEP#_ACBUS1-Pad13)") (class "Default")
      (node (ref "U12") (pin "13") (pinfunction "SLEEP#_ACBUS1_13") (pintype "output"))
    )
    (net (code "101") (name "unconnected-(U12-SLEEP#_BCBUS1-Pad29)") (class "Default")
      (node (ref "U12") (pin "29") (pinfunction "SLEEP#_BCBUS1_29") (pintype "output"))
    )
    (net (code "102") (name "unconnected-(U12-TXDEN_ACBUS0-Pad15)") (class "Default")
      (node (ref "U12") (pin "15") (pinfunction "TXDEN_ACBUS0_15") (pintype "output"))
    )
    (net (code "103") (name "unconnected-(U12-TXDEN_BCBUS0-Pad30)") (class "Default")
      (node (ref "U12") (pin "30") (pinfunction "TXDEN_BCBUS0_30") (pintype "output"))
    )
    (net (code "104") (name "unconnected-(U12-TXLED#_ACBUS3-Pad11)") (class "Default")
      (node (ref "U12") (pin "11") (pinfunction "TXLED#_ACBUS3_11") (pintype "output"))
    )
  )
)
